# Compass.net
KiCad netlist of a schematic drawn in EAGLE
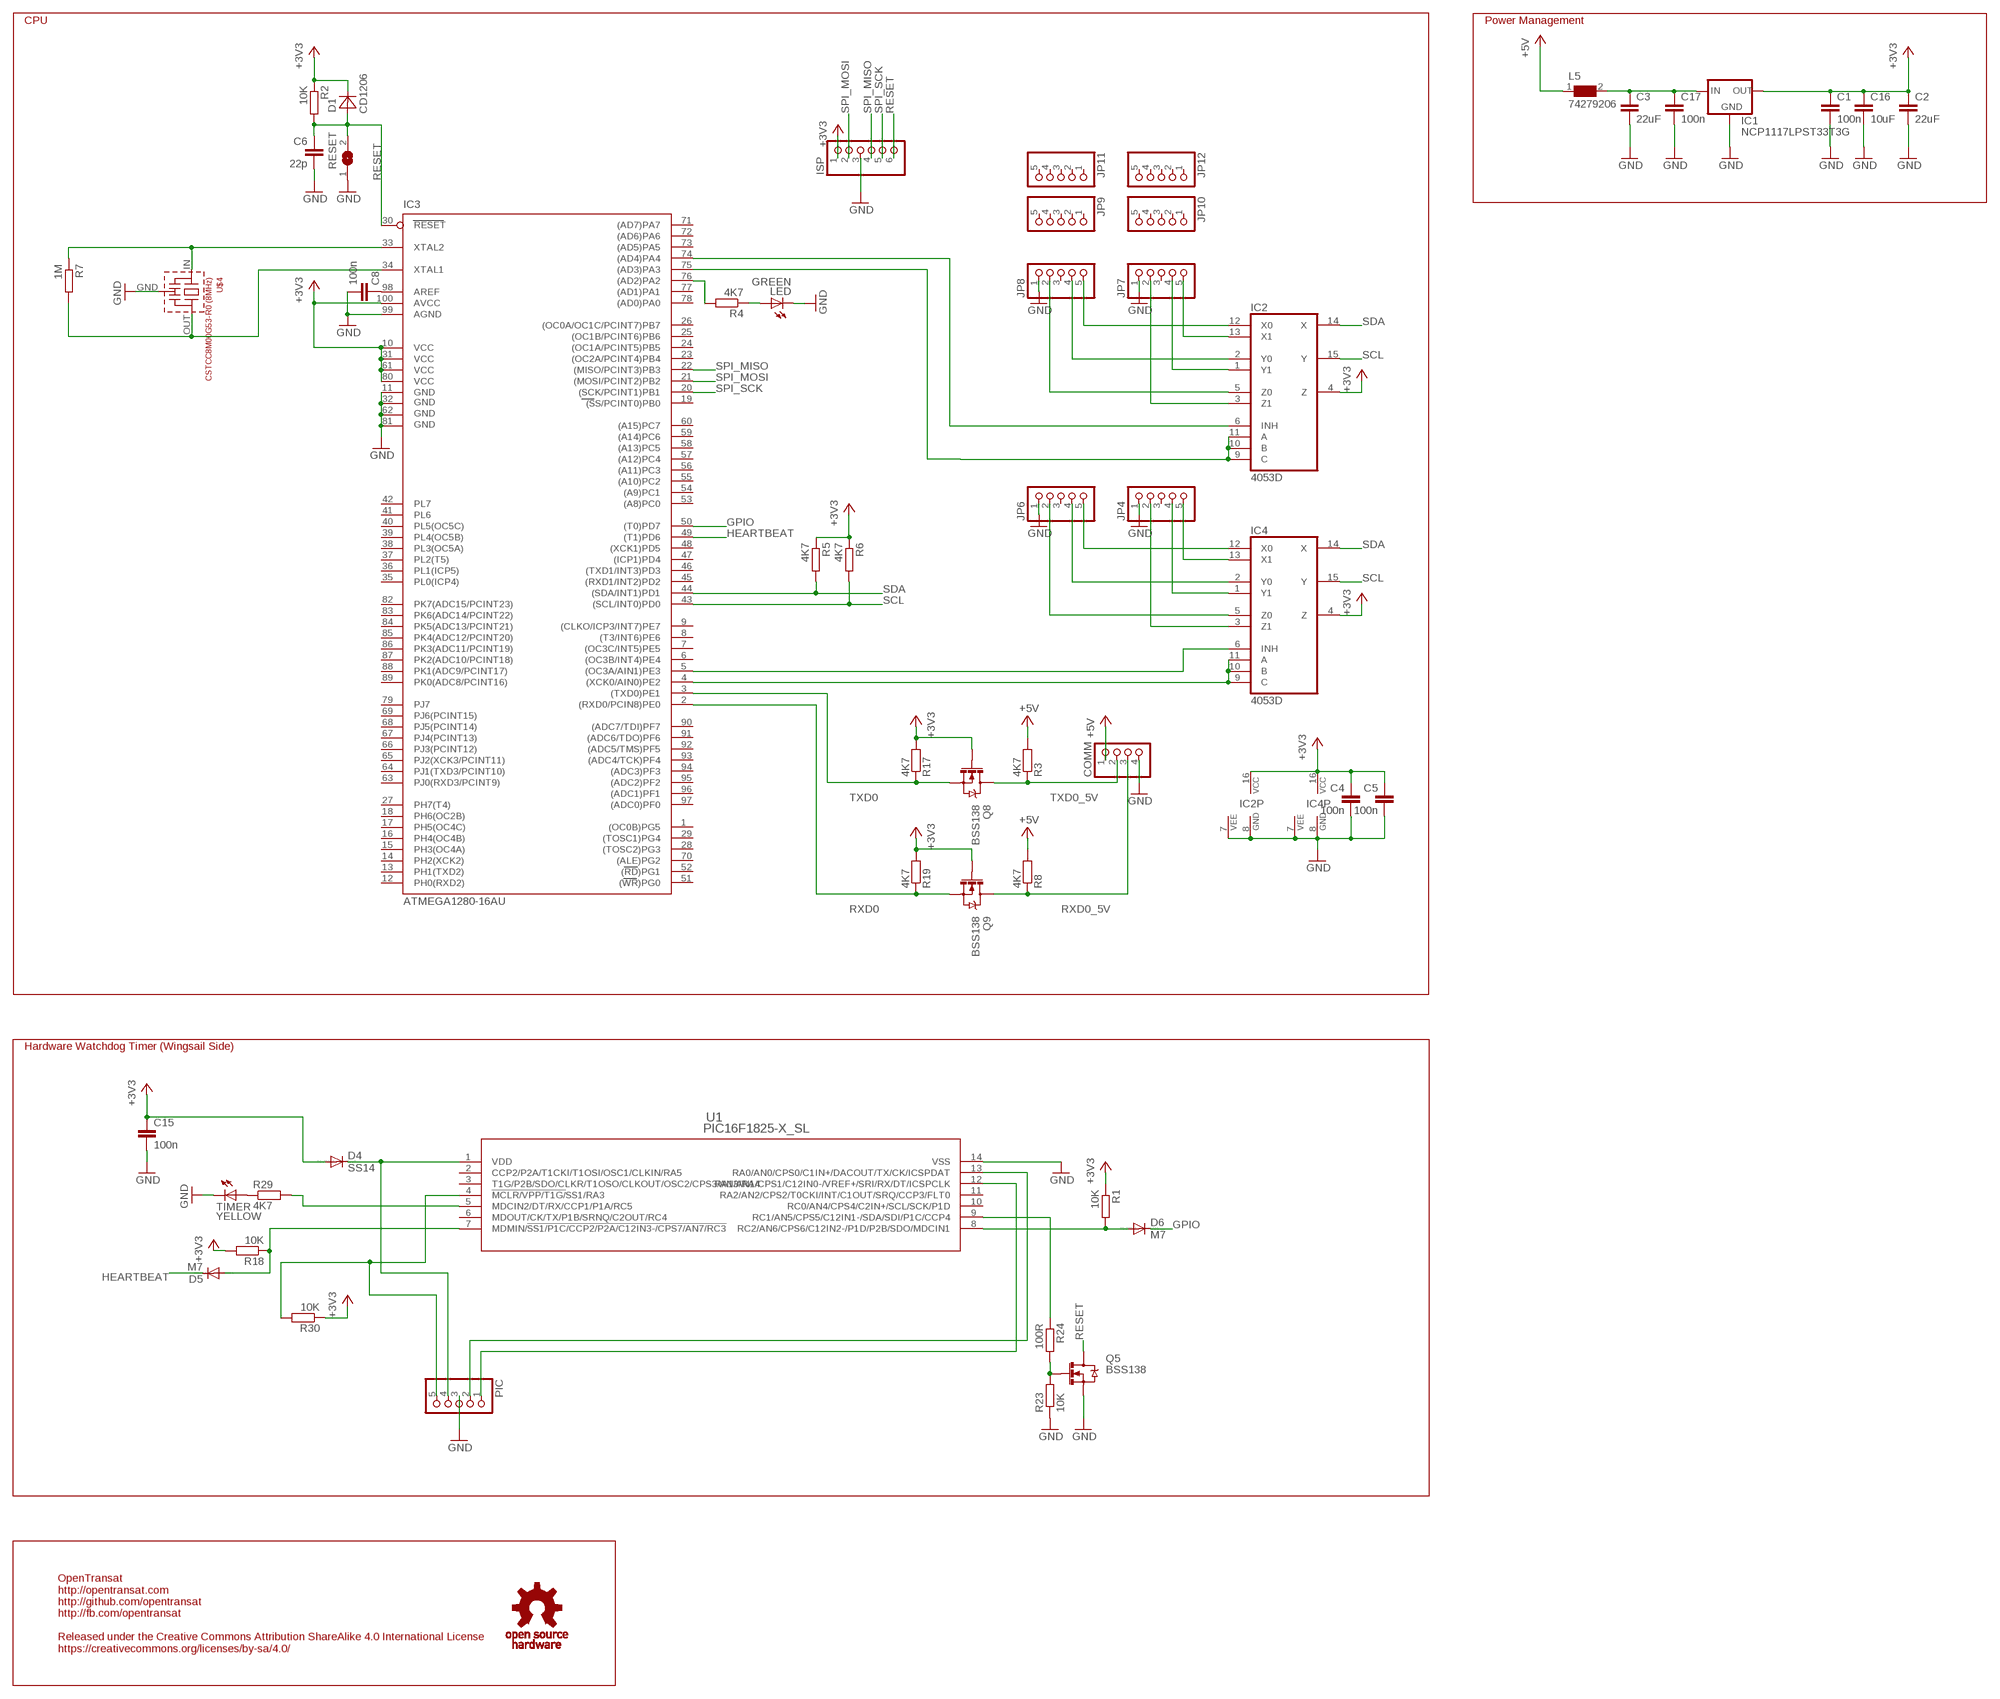
[diagram p0: schematic, sheet 1]

(export (version "E")
  (design (tool "Eeschema 10.0.6"))
  (components
    (comp (ref "C1")
      (value "100n")
      (footprint "eagle-import:C0603")
      (libsource (lib "eagle-import") (part "C-EUC0603"))
    )
    (comp (ref "C2")
      (value "22uF")
      (footprint "eagle-import:C1210")
      (libsource (lib "eagle-import") (part "C-EUC1210"))
    )
    (comp (ref "C3")
      (value "22uF")
      (footprint "eagle-import:C1210")
      (libsource (lib "eagle-import") (part "C-EUC1210"))
    )
    (comp (ref "C4")
      (value "100n")
      (footprint "eagle-import:C0603")
      (libsource (lib "eagle-import") (part "C-EUC0603"))
    )
    (comp (ref "C5")
      (value "100n")
      (footprint "eagle-import:C0603")
      (libsource (lib "eagle-import") (part "C-EUC0603"))
    )
    (comp (ref "C6")
      (value "22p")
      (footprint "eagle-import:C0603")
      (libsource (lib "eagle-import") (part "C-EUC0603"))
    )
    (comp (ref "C8")
      (value "100n")
      (footprint "eagle-import:C0603")
      (libsource (lib "eagle-import") (part "C-EUC0603"))
    )
    (comp (ref "C15")
      (value "100n")
      (footprint "eagle-import:C0603")
      (libsource (lib "eagle-import") (part "C-EUC0603"))
    )
    (comp (ref "C16")
      (value "10uF")
      (footprint "eagle-import:C1206")
      (libsource (lib "eagle-import") (part "C-EUC1206"))
    )
    (comp (ref "C17")
      (value "100n")
      (footprint "eagle-import:C0603")
      (libsource (lib "eagle-import") (part "C-EUC0603"))
    )
    (comp (ref "COMM")
      (value "PINHD-1X4/90")
      (footprint "eagle-import:1X04_90")
      (libsource (lib "eagle-import") (part "PINHD-1X4/90"))
    )
    (comp (ref "D1")
      (value "CD1206")
      (footprint "eagle-import:R1206")
      (libsource (lib "eagle-import") (part "CD1206"))
    )
    (comp (ref "D4")
      (value "SS14")
      (footprint "eagle-import:DO214AC")
      (libsource (lib "eagle-import") (part "DIODE-DO214AC"))
    )
    (comp (ref "D5")
      (value "M7")
      (footprint "eagle-import:DO-214AC")
      (libsource (lib "eagle-import") (part "DIODE-DO-214AC"))
    )
    (comp (ref "D6")
      (value "M7")
      (footprint "eagle-import:DO-214AC")
      (libsource (lib "eagle-import") (part "DIODE-DO-214AC"))
    )
    (comp (ref "IC1")
      (value "NCP1117LPST33T3G")
      (footprint "eagle-import:SOT223")
      (fields (field (name "MF") "Texas Instruments") (field (name "MPN") "LM1117MP-3.3"))
      (libsource (lib "eagle-import") (part "LM1117?-MP3.3"))
    )
    (comp (ref "IC2")
      (value "4053D")
      (footprint "eagle-import:SO16")
      (libsource (lib "eagle-import") (part "4053D"))
    )
    (comp (ref "IC3")
      (value "ATMEGA1280-16AU")
      (footprint "eagle-import:TQFP100")
      (libsource (lib "eagle-import") (part "ATMEGAAU1280-16"))
    )
    (comp (ref "IC4")
      (value "4053D")
      (footprint "eagle-import:SO16")
      (libsource (lib "eagle-import") (part "4053D"))
    )
    (comp (ref "ISP")
      (value "PINHD-1X6/90")
      (footprint "eagle-import:1X06_90")
      (libsource (lib "eagle-import") (part "PINHD-1X6/90"))
    )
    (comp (ref "JP4")
      (value "PINHD-1X5")
      (footprint "eagle-import:1X05")
      (libsource (lib "eagle-import") (part "PINHD-1X5"))
    )
    (comp (ref "JP6")
      (value "PINHD-1X5")
      (footprint "eagle-import:1X05")
      (libsource (lib "eagle-import") (part "PINHD-1X5"))
    )
    (comp (ref "JP7")
      (value "PINHD-1X5")
      (footprint "eagle-import:1X05")
      (libsource (lib "eagle-import") (part "PINHD-1X5"))
    )
    (comp (ref "JP8")
      (value "PINHD-1X5")
      (footprint "eagle-import:1X05")
      (libsource (lib "eagle-import") (part "PINHD-1X5"))
    )
    (comp (ref "JP9")
      (value "PINHD-1X5")
      (footprint "eagle-import:1X05")
      (libsource (lib "eagle-import") (part "PINHD-1X5"))
    )
    (comp (ref "JP10")
      (value "PINHD-1X5")
      (footprint "eagle-import:1X05")
      (libsource (lib "eagle-import") (part "PINHD-1X5"))
    )
    (comp (ref "JP11")
      (value "PINHD-1X5")
      (footprint "eagle-import:1X05")
      (libsource (lib "eagle-import") (part "PINHD-1X5"))
    )
    (comp (ref "JP12")
      (value "PINHD-1X5")
      (footprint "eagle-import:1X05")
      (libsource (lib "eagle-import") (part "PINHD-1X5"))
    )
    (comp (ref "L5")
      (value "74279206")
      (footprint "eagle-import:0805")
      (libsource (lib "eagle-import") (part "WE-CBF_0805"))
    )
    (comp (ref "LED")
      (value "GREEN")
      (footprint "eagle-import:CHIPLED_0805")
      (libsource (lib "eagle-import") (part "LEDCHIPLED_0805"))
    )
    (comp (ref "PIC")
      (value "PINHD-1X5/90")
      (footprint "eagle-import:1X05_90")
      (libsource (lib "eagle-import") (part "PINHD-1X5/90"))
    )
    (comp (ref "Q5")
      (value "BSS138")
      (footprint "eagle-import:SOT23-3")
      (libsource (lib "eagle-import") (part "MOSFET-NCHANNEL_SOT23-3"))
    )
    (comp (ref "Q8")
      (value "BSS138")
      (footprint "eagle-import:SOT23-3")
      (libsource (lib "eagle-import") (part "MOSFET-NCHANNEL_SOT23-3"))
    )
    (comp (ref "Q9")
      (value "BSS138")
      (footprint "eagle-import:SOT23-3")
      (libsource (lib "eagle-import") (part "MOSFET-NCHANNEL_SOT23-3"))
    )
    (comp (ref "R1")
      (value "10K")
      (footprint "eagle-import:R0603")
      (libsource (lib "eagle-import") (part "R-EU_R0603"))
    )
    (comp (ref "R2")
      (value "10K")
      (footprint "eagle-import:R0603")
      (libsource (lib "eagle-import") (part "R-EU_R0603"))
    )
    (comp (ref "R3")
      (value "4K7")
      (footprint "eagle-import:R0603")
      (libsource (lib "eagle-import") (part "R-EU_R0603"))
    )
    (comp (ref "R4")
      (value "4K7")
      (footprint "eagle-import:R0603")
      (libsource (lib "eagle-import") (part "R-EU_R0603"))
    )
    (comp (ref "R5")
      (value "4K7")
      (footprint "eagle-import:R0603")
      (libsource (lib "eagle-import") (part "R-EU_R0603"))
    )
    (comp (ref "R6")
      (value "4K7")
      (footprint "eagle-import:R0603")
      (libsource (lib "eagle-import") (part "R-EU_R0603"))
    )
    (comp (ref "R7")
      (value "1M")
      (footprint "eagle-import:R0603")
      (libsource (lib "eagle-import") (part "R-EU_R0603"))
    )
    (comp (ref "R8")
      (value "4K7")
      (footprint "eagle-import:R0603")
      (libsource (lib "eagle-import") (part "R-EU_R0603"))
    )
    (comp (ref "R17")
      (value "4K7")
      (footprint "eagle-import:R0603")
      (libsource (lib "eagle-import") (part "R-EU_R0603"))
    )
    (comp (ref "R18")
      (value "10K")
      (footprint "eagle-import:R0603")
      (libsource (lib "eagle-import") (part "R-EU_R0603"))
    )
    (comp (ref "R19")
      (value "4K7")
      (footprint "eagle-import:R0603")
      (libsource (lib "eagle-import") (part "R-EU_R0603"))
    )
    (comp (ref "R23")
      (value "10K")
      (footprint "eagle-import:R0603")
      (libsource (lib "eagle-import") (part "R-EU_R0603"))
    )
    (comp (ref "R24")
      (value "100R")
      (footprint "eagle-import:R0603")
      (libsource (lib "eagle-import") (part "R-EU_R0603"))
    )
    (comp (ref "R29")
      (value "4K7")
      (footprint "eagle-import:R0603")
      (libsource (lib "eagle-import") (part "R-EU_R0603"))
    )
    (comp (ref "R30")
      (value "10K")
      (footprint "eagle-import:R0603")
      (libsource (lib "eagle-import") (part "R-EU_R0603"))
    )
    (comp (ref "RESET")
      (value "SJW")
      (footprint "eagle-import:SJW")
      (libsource (lib "eagle-import") (part "SJW"))
    )
    (comp (ref "TIMER")
      (value "YELLOW")
      (footprint "eagle-import:CHIPLED_0805")
      (libsource (lib "eagle-import") (part "LEDCHIPLED_0805"))
    )
    (comp (ref "U$1")
      (value "OSHW_S")
      (footprint "eagle-import:OSHWS")
      (libsource (lib "eagle-import") (part "OSHW_S"))
    )
    (comp (ref "U$4")
      (value "CSTCC8M00G53-R0 (8MHz)")
      (footprint "eagle-import:CSTCC")
      (libsource (lib "eagle-import") (part "CSTCC"))
    )
    (comp (ref "U1")
      (value "PIC16F1825-X_SL")
      (footprint "eagle-import:SOIC14-N_MC")
      (libsource (lib "eagle-import") (part "PIC16F1825-X_SL"))
    )
  )
  (nets
    (net (code "1") (name "+3V3") (class "Default")
      (node (ref "C1") (pin "1") (pinfunction "1_1") (pintype "passive"))
      (node (ref "C15") (pin "1") (pinfunction "1_1") (pintype "passive"))
      (node (ref "C16") (pin "1") (pinfunction "1_1") (pintype "passive"))
      (node (ref "C2") (pin "1") (pinfunction "1_1") (pintype "passive"))
      (node (ref "C4") (pin "1") (pinfunction "1_1") (pintype "passive"))
      (node (ref "C5") (pin "1") (pinfunction "1_1") (pintype "passive"))
      (node (ref "D1") (pin "2") (pinfunction "C_2") (pintype "passive"))
      (node (ref "D4") (pin "A") (pinfunction "A_A") (pintype "passive"))
      (node (ref "IC1") (pin "2") (pinfunction "OUT_2") (pintype "passive"))
      (node (ref "IC1") (pin "4") (pinfunction "OUT_4") (pintype "passive"))
      (node (ref "IC2") (pin "16") (pinfunction "VCC_16") (pintype "power_in"))
      (node (ref "IC2") (pin "4") (pinfunction "Z_4") (pintype "bidirectional"))
      (node (ref "IC3") (pin "10") (pinfunction "VCC_10") (pintype "power_in"))
      (node (ref "IC3") (pin "100") (pinfunction "AVCC_100") (pintype "power_in"))
      (node (ref "IC3") (pin "31") (pinfunction "VCC1_31") (pintype "power_in"))
      (node (ref "IC3") (pin "61") (pinfunction "VCC2_61") (pintype "power_in"))
      (node (ref "IC3") (pin "80") (pinfunction "VCC3_80") (pintype "power_in"))
      (node (ref "IC4") (pin "16") (pinfunction "VCC_16") (pintype "power_in"))
      (node (ref "IC4") (pin "4") (pinfunction "Z_4") (pintype "bidirectional"))
      (node (ref "ISP") (pin "1") (pinfunction "1_1") (pintype "passive"))
      (node (ref "Q8") (pin "1") (pinfunction "G_1") (pintype "passive"))
      (node (ref "Q9") (pin "1") (pinfunction "G_1") (pintype "passive"))
      (node (ref "R1") (pin "1") (pinfunction "1_1") (pintype "passive"))
      (node (ref "R17") (pin "2") (pinfunction "2_2") (pintype "passive"))
      (node (ref "R18") (pin "2") (pinfunction "2_2") (pintype "passive"))
      (node (ref "R19") (pin "2") (pinfunction "2_2") (pintype "passive"))
      (node (ref "R2") (pin "1") (pinfunction "1_1") (pintype "passive"))
      (node (ref "R30") (pin "1") (pinfunction "1_1") (pintype "passive"))
      (node (ref "R5") (pin "1") (pinfunction "1_1") (pintype "passive"))
      (node (ref "R6") (pin "1") (pinfunction "1_1") (pintype "passive"))
    )
    (net (code "2") (name "+5V") (class "Default")
      (node (ref "COMM") (pin "1") (pinfunction "1_1") (pintype "passive"))
      (node (ref "L5") (pin "1") (pinfunction "1_1") (pintype "passive"))
      (node (ref "R3") (pin "2") (pinfunction "2_2") (pintype "passive"))
      (node (ref "R8") (pin "2") (pinfunction "2_2") (pintype "passive"))
    )
    (net (code "3") (name "/GPIO") (class "Default")
      (node (ref "D6") (pin "C") (pinfunction "C_C") (pintype "passive"))
      (node (ref "IC3") (pin "50") (pinfunction "(T0)PD7_50") (pintype "bidirectional"))
    )
    (net (code "4") (name "/HEARTBEAT") (class "Default")
      (node (ref "D5") (pin "C") (pinfunction "C_C") (pintype "passive"))
      (node (ref "IC3") (pin "49") (pinfunction "(T1)PD6_49") (pintype "bidirectional"))
    )
    (net (code "5") (name "/RESET") (class "Default")
      (node (ref "C6") (pin "1") (pinfunction "1_1") (pintype "passive"))
      (node (ref "D1") (pin "1") (pinfunction "A_1") (pintype "passive"))
      (node (ref "IC3") (pin "30") (pinfunction "RESET_30") (pintype "input"))
      (node (ref "ISP") (pin "6") (pinfunction "6_6") (pintype "passive"))
      (node (ref "Q5") (pin "3") (pinfunction "D_3") (pintype "passive"))
      (node (ref "R2") (pin "2") (pinfunction "2_2") (pintype "passive"))
      (node (ref "RESET") (pin "2") (pinfunction "2_2") (pintype "passive"))
    )
    (net (code "6") (name "/RXD0") (class "Default")
      (node (ref "IC3") (pin "2") (pinfunction "(RXD0/PCIN8)PE0_2") (pintype "bidirectional"))
      (node (ref "Q9") (pin "2") (pinfunction "S_2") (pintype "passive"))
      (node (ref "R19") (pin "1") (pinfunction "1_1") (pintype "passive"))
    )
    (net (code "7") (name "/RXD0_5V") (class "Default")
      (node (ref "COMM") (pin "3") (pinfunction "3_3") (pintype "passive"))
      (node (ref "Q9") (pin "3") (pinfunction "D_3") (pintype "passive"))
      (node (ref "R8") (pin "1") (pinfunction "1_1") (pintype "passive"))
    )
    (net (code "8") (name "/SCL") (class "Default")
      (node (ref "IC2") (pin "15") (pinfunction "Y_15") (pintype "bidirectional"))
      (node (ref "IC3") (pin "43") (pinfunction "(SCL/INT0)PD0_43") (pintype "bidirectional"))
      (node (ref "IC4") (pin "15") (pinfunction "Y_15") (pintype "bidirectional"))
      (node (ref "R6") (pin "2") (pinfunction "2_2") (pintype "passive"))
    )
    (net (code "9") (name "/SDA") (class "Default")
      (node (ref "IC2") (pin "14") (pinfunction "X_14") (pintype "bidirectional"))
      (node (ref "IC3") (pin "44") (pinfunction "(SDA/INT1)PD1_44") (pintype "bidirectional"))
      (node (ref "IC4") (pin "14") (pinfunction "X_14") (pintype "bidirectional"))
      (node (ref "R5") (pin "2") (pinfunction "2_2") (pintype "passive"))
    )
    (net (code "10") (name "/SPI_MISO") (class "Default")
      (node (ref "IC3") (pin "22") (pinfunction "(MISO/PCINT3)PB3_22") (pintype "bidirectional"))
      (node (ref "ISP") (pin "4") (pinfunction "4_4") (pintype "passive"))
    )
    (net (code "11") (name "/SPI_MOSI") (class "Default")
      (node (ref "IC3") (pin "21") (pinfunction "(MOSI/PCINT2)PB2_21") (pintype "bidirectional"))
      (node (ref "ISP") (pin "2") (pinfunction "2_2") (pintype "passive"))
    )
    (net (code "12") (name "/SPI_SCK") (class "Default")
      (node (ref "IC3") (pin "20") (pinfunction "(SCK/PCINT1)PB1_20") (pintype "bidirectional"))
      (node (ref "ISP") (pin "5") (pinfunction "5_5") (pintype "passive"))
    )
    (net (code "13") (name "/TXD0") (class "Default")
      (node (ref "IC3") (pin "3") (pinfunction "(TXD0)PE1_3") (pintype "bidirectional"))
      (node (ref "Q8") (pin "2") (pinfunction "S_2") (pintype "passive"))
      (node (ref "R17") (pin "1") (pinfunction "1_1") (pintype "passive"))
    )
    (net (code "14") (name "/TXD0_5V") (class "Default")
      (node (ref "COMM") (pin "2") (pinfunction "2_2") (pintype "passive"))
      (node (ref "Q8") (pin "3") (pinfunction "D_3") (pintype "passive"))
      (node (ref "R3") (pin "1") (pinfunction "1_1") (pintype "passive"))
    )
    (net (code "15") (name "GND") (class "Default")
      (node (ref "C1") (pin "2") (pinfunction "2_2") (pintype "passive"))
      (node (ref "C15") (pin "2") (pinfunction "2_2") (pintype "passive"))
      (node (ref "C16") (pin "2") (pinfunction "2_2") (pintype "passive"))
      (node (ref "C17") (pin "2") (pinfunction "2_2") (pintype "passive"))
      (node (ref "C2") (pin "2") (pinfunction "2_2") (pintype "passive"))
      (node (ref "C3") (pin "2") (pinfunction "2_2") (pintype "passive"))
      (node (ref "C4") (pin "2") (pinfunction "2_2") (pintype "passive"))
      (node (ref "C5") (pin "2") (pinfunction "2_2") (pintype "passive"))
      (node (ref "C6") (pin "2") (pinfunction "2_2") (pintype "passive"))
      (node (ref "C8") (pin "2") (pinfunction "2_2") (pintype "passive"))
      (node (ref "COMM") (pin "4") (pinfunction "4_4") (pintype "passive"))
      (node (ref "IC1") (pin "1") (pinfunction "GND_1") (pintype "input"))
      (node (ref "IC2") (pin "7") (pinfunction "VEE_7") (pintype "power_in"))
      (node (ref "IC2") (pin "8") (pinfunction "GND_8") (pintype "power_in"))
      (node (ref "IC3") (pin "11") (pinfunction "GND_11") (pintype "power_in"))
      (node (ref "IC3") (pin "32") (pinfunction "GND1_32") (pintype "power_in"))
      (node (ref "IC3") (pin "62") (pinfunction "GND2_62") (pintype "power_in"))
      (node (ref "IC3") (pin "81") (pinfunction "GND3_81") (pintype "power_in"))
      (node (ref "IC3") (pin "99") (pinfunction "AGND_99") (pintype "power_in"))
      (node (ref "IC4") (pin "7") (pinfunction "VEE_7") (pintype "power_in"))
      (node (ref "IC4") (pin "8") (pinfunction "GND_8") (pintype "power_in"))
      (node (ref "ISP") (pin "3") (pinfunction "3_3") (pintype "passive"))
      (node (ref "JP4") (pin "1") (pinfunction "1_1") (pintype "passive"))
      (node (ref "JP6") (pin "1") (pinfunction "1_1") (pintype "passive"))
      (node (ref "JP7") (pin "1") (pinfunction "1_1") (pintype "passive"))
      (node (ref "JP8") (pin "1") (pinfunction "1_1") (pintype "passive"))
      (node (ref "LED") (pin "C") (pinfunction "C_C") (pintype "passive"))
      (node (ref "PIC") (pin "3") (pinfunction "3_3") (pintype "passive"))
      (node (ref "Q5") (pin "2") (pinfunction "S_2") (pintype "passive"))
      (node (ref "R23") (pin "1") (pinfunction "1_1") (pintype "passive"))
      (node (ref "RESET") (pin "1") (pinfunction "1_1") (pintype "passive"))
      (node (ref "TIMER") (pin "C") (pinfunction "C_C") (pintype "passive"))
      (node (ref "U$4") (pin "GND") (pinfunction "GND_GND") (pintype "power_in"))
      (node (ref "U1") (pin "14") (pinfunction "VSS_14") (pintype "power_in"))
    )
    (net (code "16") (name "Net-(IC1-IN)") (class "Default")
      (node (ref "C17") (pin "1") (pinfunction "1_1") (pintype "passive"))
      (node (ref "C3") (pin "1") (pinfunction "1_1") (pintype "passive"))
      (node (ref "IC1") (pin "3") (pinfunction "IN_3") (pintype "input"))
      (node (ref "L5") (pin "2") (pinfunction "2_2") (pintype "passive"))
    )
    (net (code "17") (name "Net-(IC2A-A)") (class "Default")
      (node (ref "IC2") (pin "10") (pinfunction "B_10") (pintype "input"))
      (node (ref "IC2") (pin "11") (pinfunction "A_11") (pintype "input"))
      (node (ref "IC2") (pin "9") (pinfunction "C_9") (pintype "input"))
      (node (ref "IC3") (pin "75") (pinfunction "(AD3)PA3_75") (pintype "bidirectional"))
    )
    (net (code "18") (name "Net-(IC2A-INH)") (class "Default")
      (node (ref "IC2") (pin "6") (pinfunction "INH_6") (pintype "input"))
      (node (ref "IC3") (pin "74") (pinfunction "(AD4)PA4_74") (pintype "bidirectional"))
    )
    (net (code "19") (name "Net-(IC2A-X0)") (class "Default")
      (node (ref "IC2") (pin "12") (pinfunction "X0_12") (pintype "bidirectional"))
      (node (ref "JP8") (pin "5") (pinfunction "5_5") (pintype "passive"))
    )
    (net (code "20") (name "Net-(IC2A-X1)") (class "Default")
      (node (ref "IC2") (pin "13") (pinfunction "X1_13") (pintype "bidirectional"))
      (node (ref "JP7") (pin "5") (pinfunction "5_5") (pintype "passive"))
    )
    (net (code "21") (name "Net-(IC2A-Y0)") (class "Default")
      (node (ref "IC2") (pin "2") (pinfunction "Y0_2") (pintype "bidirectional"))
      (node (ref "JP8") (pin "4") (pinfunction "4_4") (pintype "passive"))
    )
    (net (code "22") (name "Net-(IC2A-Y1)") (class "Default")
      (node (ref "IC2") (pin "1") (pinfunction "Y1_1") (pintype "bidirectional"))
      (node (ref "JP7") (pin "4") (pinfunction "4_4") (pintype "passive"))
    )
    (net (code "23") (name "Net-(IC2A-Z0)") (class "Default")
      (node (ref "IC2") (pin "5") (pinfunction "Z0_5") (pintype "bidirectional"))
      (node (ref "JP8") (pin "2") (pinfunction "2_2") (pintype "passive"))
    )
    (net (code "24") (name "Net-(IC2A-Z1)") (class "Default")
      (node (ref "IC2") (pin "3") (pinfunction "Z1_3") (pintype "bidirectional"))
      (node (ref "JP7") (pin "2") (pinfunction "2_2") (pintype "passive"))
    )
    (net (code "25") (name "Net-(IC3-(AD2)PA2)") (class "Default")
      (node (ref "IC3") (pin "76") (pinfunction "(AD2)PA2_76") (pintype "bidirectional"))
      (node (ref "R4") (pin "2") (pinfunction "2_2") (pintype "passive"))
    )
    (net (code "26") (name "Net-(IC3-(OC3A{slash}AIN1)PE3)") (class "Default")
      (node (ref "IC3") (pin "5") (pinfunction "(OC3A/AIN1)PE3_5") (pintype "bidirectional"))
      (node (ref "IC4") (pin "6") (pinfunction "INH_6") (pintype "input"))
    )
    (net (code "27") (name "Net-(IC3-(XCK0{slash}AIN0)PE2)") (class "Default")
      (node (ref "IC3") (pin "4") (pinfunction "(XCK0/AIN0)PE2_4") (pintype "bidirectional"))
      (node (ref "IC4") (pin "10") (pinfunction "B_10") (pintype "input"))
      (node (ref "IC4") (pin "11") (pinfunction "A_11") (pintype "input"))
      (node (ref "IC4") (pin "9") (pinfunction "C_9") (pintype "input"))
    )
    (net (code "28") (name "Net-(IC3-AREF)") (class "Default")
      (node (ref "C8") (pin "1") (pinfunction "1_1") (pintype "passive"))
      (node (ref "IC3") (pin "98") (pinfunction "AREF_98") (pintype "bidirectional"))
    )
    (net (code "29") (name "Net-(IC3-XTAL1)") (class "Default")
      (node (ref "IC3") (pin "34") (pinfunction "XTAL1_34") (pintype "input"))
      (node (ref "R7") (pin "2") (pinfunction "2_2") (pintype "passive"))
      (node (ref "U$4") (pin "OUT") (pinfunction "OUT_OUT") (pintype "output"))
    )
    (net (code "30") (name "Net-(IC3-XTAL2)") (class "Default")
      (node (ref "IC3") (pin "33") (pinfunction "XTAL2_33") (pintype "output"))
      (node (ref "R7") (pin "1") (pinfunction "1_1") (pintype "passive"))
      (node (ref "U$4") (pin "IN") (pinfunction "IN_IN") (pintype "input"))
    )
    (net (code "31") (name "Net-(IC4A-X0)") (class "Default")
      (node (ref "IC4") (pin "12") (pinfunction "X0_12") (pintype "bidirectional"))
      (node (ref "JP6") (pin "5") (pinfunction "5_5") (pintype "passive"))
    )
    (net (code "32") (name "Net-(IC4A-X1)") (class "Default")
      (node (ref "IC4") (pin "13") (pinfunction "X1_13") (pintype "bidirectional"))
      (node (ref "JP4") (pin "5") (pinfunction "5_5") (pintype "passive"))
    )
    (net (code "33") (name "Net-(IC4A-Y0)") (class "Default")
      (node (ref "IC4") (pin "2") (pinfunction "Y0_2") (pintype "bidirectional"))
      (node (ref "JP6") (pin "4") (pinfunction "4_4") (pintype "passive"))
    )
    (net (code "34") (name "Net-(IC4A-Y1)") (class "Default")
      (node (ref "IC4") (pin "1") (pinfunction "Y1_1") (pintype "bidirectional"))
      (node (ref "JP4") (pin "4") (pinfunction "4_4") (pintype "passive"))
    )
    (net (code "35") (name "Net-(IC4A-Z0)") (class "Default")
      (node (ref "IC4") (pin "5") (pinfunction "Z0_5") (pintype "bidirectional"))
      (node (ref "JP6") (pin "2") (pinfunction "2_2") (pintype "passive"))
    )
    (net (code "36") (name "Net-(IC4A-Z1)") (class "Default")
      (node (ref "IC4") (pin "3") (pinfunction "Z1_3") (pintype "bidirectional"))
      (node (ref "JP4") (pin "2") (pinfunction "2_2") (pintype "passive"))
    )
    (net (code "37") (name "Net-(LED-PadA)") (class "Default")
      (node (ref "LED") (pin "A") (pinfunction "A_A") (pintype "passive"))
      (node (ref "R4") (pin "1") (pinfunction "1_1") (pintype "passive"))
    )
    (net (code "38") (name "Net-(Q5-G)") (class "Default")
      (node (ref "Q5") (pin "1") (pinfunction "G_1") (pintype "passive"))
      (node (ref "R23") (pin "2") (pinfunction "2_2") (pintype "passive"))
      (node (ref "R24") (pin "2") (pinfunction "2_2") (pintype "passive"))
    )
    (net (code "39") (name "Net-(R29-Pad1)") (class "Default")
      (node (ref "R29") (pin "1") (pinfunction "1_1") (pintype "passive"))
      (node (ref "TIMER") (pin "A") (pinfunction "A_A") (pintype "passive"))
    )
    (net (code "40") (name "Net-(U1-MDCIN2{slash}DT{slash}RX{slash}CCP1{slash}P1A{slash}RC5)") (class "Default")
      (node (ref "R29") (pin "2") (pinfunction "2_2") (pintype "passive"))
      (node (ref "U1") (pin "5") (pinfunction "MDCIN2/DT/RX/CCP1/P1A/RC5_5") (pintype "bidirectional"))
    )
    (net (code "41") (name "Net-(U1-MDMIN{slash}~{SS1{slash}P1C{slash}CCP2{slash}P2A{slash}C12IN3-{slash}CPS7{slash}AN7{slash}RC3})") (class "Default")
      (node (ref "D5") (pin "A") (pinfunction "A_A") (pintype "passive"))
      (node (ref "R18") (pin "1") (pinfunction "1_1") (pintype "passive"))
      (node (ref "U1") (pin "7") (pinfunction "MDMIN/~{SS1/P1C/CCP2/P2A/C12IN3-/CPS7/AN7/RC3}_7") (pintype "bidirectional"))
    )
    (net (code "42") (name "Net-(U1-RA0{slash}AN0{slash}CPS0{slash}C1IN+{slash}DACOUT{slash}TX{slash}CK{slash}ICSPDAT)") (class "Default")
      (node (ref "PIC") (pin "2") (pinfunction "2_2") (pintype "passive"))
      (node (ref "U1") (pin "13") (pinfunction "RA0/AN0/CPS0/C1IN+/DACOUT/TX/CK/ICSPDAT_13") (pintype "bidirectional"))
    )
    (net (code "43") (name "Net-(U1-RA1{slash}AN1{slash}CPS1{slash}C12IN0-{slash}VREF+{slash}SRI{slash}RX{slash}DT{slash}ICSPCLK)") (class "Default")
      (node (ref "PIC") (pin "1") (pinfunction "1_1") (pintype "passive"))
      (node (ref "U1") (pin "12") (pinfunction "RA1/AN1/CPS1/C12IN0-/VREF+/SRI/RX/DT/ICSPCLK_12") (pintype "bidirectional"))
    )
    (net (code "44") (name "Net-(U1-RC1{slash}AN5{slash}CPS5{slash}C12IN1-{slash}SDA{slash}SDI{slash}P1C{slash}CCP4)") (class "Default")
      (node (ref "R24") (pin "1") (pinfunction "1_1") (pintype "passive"))
      (node (ref "U1") (pin "9") (pinfunction "RC1/AN5/CPS5/C12IN1-/SDA/SDI/P1C/CCP4_9") (pintype "bidirectional"))
    )
    (net (code "45") (name "Net-(U1-RC2{slash}AN6{slash}CPS6{slash}C12IN2-{slash}P1D{slash}P2B{slash}SDO{slash}MDCIN1)") (class "Default")
      (node (ref "D6") (pin "A") (pinfunction "A_A") (pintype "passive"))
      (node (ref "R1") (pin "2") (pinfunction "2_2") (pintype "passive"))
      (node (ref "U1") (pin "8") (pinfunction "RC2/AN6/CPS6/C12IN2-/P1D/P2B/SDO/MDCIN1_8") (pintype "bidirectional"))
    )
    (net (code "46") (name "Net-(U1-VDD)") (class "Default")
      (node (ref "D4") (pin "C") (pinfunction "C_C") (pintype "passive"))
      (node (ref "PIC") (pin "4") (pinfunction "4_4") (pintype "passive"))
      (node (ref "U1") (pin "1") (pinfunction "VDD_1") (pintype "power_in"))
    )
    (net (code "47") (name "Net-(U1-~{MCLR{slash}VPP{slash}T1G{slash}}SS1{slash}RA3)") (class "Default")
      (node (ref "PIC") (pin "5") (pinfunction "5_5") (pintype "passive"))
      (node (ref "R30") (pin "2") (pinfunction "2_2") (pintype "passive"))
      (node (ref "U1") (pin "4") (pinfunction "~{MCLR/VPP/T1G/}SS1/RA3_4") (pintype "bidirectional"))
    )
    (net (code "48") (name "unconnected-(IC3-(A8)PC0-Pad53)") (class "Default")
      (node (ref "IC3") (pin "53") (pinfunction "(A8)PC0_53") (pintype "bidirectional"))
    )
    (net (code "49") (name "unconnected-(IC3-(A9)PC1-Pad54)") (class "Default")
      (node (ref "IC3") (pin "54") (pinfunction "(A9)PC1_54") (pintype "bidirectional"))
    )
    (net (code "50") (name "unconnected-(IC3-(A10)PC2-Pad55)") (class "Default")
      (node (ref "IC3") (pin "55") (pinfunction "(A10)PC2_55") (pintype "bidirectional"))
    )
    (net (code "51") (name "unconnected-(IC3-(A11)PC3-Pad56)") (class "Default")
      (node (ref "IC3") (pin "56") (pinfunction "(A11)PC3_56") (pintype "bidirectional"))
    )
    (net (code "52") (name "unconnected-(IC3-(A12)PC4-Pad57)") (class "Default")
      (node (ref "IC3") (pin "57") (pinfunction "(A12)PC4_57") (pintype "bidirectional"))
    )
    (net (code "53") (name "unconnected-(IC3-(A13)PC5-Pad58)") (class "Default")
      (node (ref "IC3") (pin "58") (pinfunction "(A13)PC5_58") (pintype "bidirectional"))
    )
    (net (code "54") (name "unconnected-(IC3-(A14)PC6-Pad59)") (class "Default")
      (node (ref "IC3") (pin "59") (pinfunction "(A14)PC6_59") (pintype "bidirectional"))
    )
    (net (code "55") (name "unconnected-(IC3-(A15)PC7-Pad60)") (class "Default")
      (node (ref "IC3") (pin "60") (pinfunction "(A15)PC7_60") (pintype "bidirectional"))
    )
    (net (code "56") (name "unconnected-(IC3-(AD0)PA0-Pad78)") (class "Default")
      (node (ref "IC3") (pin "78") (pinfunction "(AD0)PA0_78") (pintype "bidirectional"))
    )
    (net (code "57") (name "unconnected-(IC3-(AD1)PA1-Pad77)") (class "Default")
      (node (ref "IC3") (pin "77") (pinfunction "(AD1)PA1_77") (pintype "bidirectional"))
    )
    (net (code "58") (name "unconnected-(IC3-(AD5)PA5-Pad73)") (class "Default")
      (node (ref "IC3") (pin "73") (pinfunction "(AD5)PA5_73") (pintype "bidirectional"))
    )
    (net (code "59") (name "unconnected-(IC3-(AD6)PA6-Pad72)") (class "Default")
      (node (ref "IC3") (pin "72") (pinfunction "(AD6)PA6_72") (pintype "bidirectional"))
    )
    (net (code "60") (name "unconnected-(IC3-(AD7)PA7-Pad71)") (class "Default")
      (node (ref "IC3") (pin "71") (pinfunction "(AD7)PA7_71") (pintype "bidirectional"))
    )
    (net (code "61") (name "unconnected-(IC3-(ADC0)PF0-Pad97)") (class "Default")
      (node (ref "IC3") (pin "97") (pinfunction "(ADC0)PF0_97") (pintype "bidirectional"))
    )
    (net (code "62") (name "unconnected-(IC3-(ADC1)PF1-Pad96)") (class "Default")
      (node (ref "IC3") (pin "96") (pinfunction "(ADC1)PF1_96") (pintype "bidirectional"))
    )
    (net (code "63") (name "unconnected-(IC3-(ADC2)PF2-Pad95)") (class "Default")
      (node (ref "IC3") (pin "95") (pinfunction "(ADC2)PF2_95") (pintype "bidirectional"))
    )
    (net (code "64") (name "unconnected-(IC3-(ADC3)PF3-Pad94)") (class "Default")
      (node (ref "IC3") (pin "94") (pinfunction "(ADC3)PF3_94") (pintype "bidirectional"))
    )
    (net (code "65") (name "unconnected-(IC3-(ADC4{slash}TCK)PF4-Pad93)") (class "Default")
      (node (ref "IC3") (pin "93") (pinfunction "(ADC4/TCK)PF4_93") (pintype "bidirectional"))
    )
    (net (code "66") (name "unconnected-(IC3-(ADC5{slash}TMS)PF5-Pad92)") (class "Default")
      (node (ref "IC3") (pin "92") (pinfunction "(ADC5/TMS)PF5_92") (pintype "bidirectional"))
    )
    (net (code "67") (name "unconnected-(IC3-(ADC6{slash}TDO)PF6-Pad91)") (class "Default")
      (node (ref "IC3") (pin "91") (pinfunction "(ADC6/TDO)PF6_91") (pintype "bidirectional"))
    )
    (net (code "68") (name "unconnected-(IC3-(ADC7{slash}TDI)PF7-Pad90)") (class "Default")
      (node (ref "IC3") (pin "90") (pinfunction "(ADC7/TDI)PF7_90") (pintype "bidirectional"))
    )
    (net (code "69") (name "unconnected-(IC3-(ALE)PG2-Pad70)") (class "Default")
      (node (ref "IC3") (pin "70") (pinfunction "(ALE)PG2_70") (pintype "bidirectional"))
    )
    (net (code "70") (name "unconnected-(IC3-(CLKO{slash}ICP3{slash}INT7)PE7-Pad9)") (class "Default")
      (node (ref "IC3") (pin "9") (pinfunction "(CLKO/ICP3/INT7)PE7_9") (pintype "bidirectional"))
    )
    (net (code "71") (name "unconnected-(IC3-(ICP1)PD4-Pad47)") (class "Default")
      (node (ref "IC3") (pin "47") (pinfunction "(ICP1)PD4_47") (pintype "bidirectional"))
    )
    (net (code "72") (name "unconnected-(IC3-(OC0A{slash}OC1C{slash}PCINT7)PB7-Pad26)") (class "Default")
      (node (ref "IC3") (pin "26") (pinfunction "(OC0A/OC1C/PCINT7)PB7_26") (pintype "bidirectional"))
    )
    (net (code "73") (name "unconnected-(IC3-(OC0B)PG5-Pad1)") (class "Default")
      (node (ref "IC3") (pin "1") (pinfunction "(OC0B)PG5_1") (pintype "bidirectional"))
    )
    (net (code "74") (name "unconnected-(IC3-(OC1A{slash}PCINT5)PB5-Pad24)") (class "Default")
      (node (ref "IC3") (pin "24") (pinfunction "(OC1A/PCINT5)PB5_24") (pintype "bidirectional"))
    )
    (net (code "75") (name "unconnected-(IC3-(OC1B{slash}PCINT6)PB6-Pad25)") (class "Default")
      (node (ref "IC3") (pin "25") (pinfunction "(OC1B/PCINT6)PB6_25") (pintype "bidirectional"))
    )
    (net (code "76") (name "unconnected-(IC3-(OC2A{slash}PCINT4)PB4-Pad23)") (class "Default")
      (node (ref "IC3") (pin "23") (pinfunction "(OC2A/PCINT4)PB4_23") (pintype "bidirectional"))
    )
    (net (code "77") (name "unconnected-(IC3-(OC3B{slash}INT4)PE4-Pad6)") (class "Default")
      (node (ref "IC3") (pin "6") (pinfunction "(OC3B/INT4)PE4_6") (pintype "bidirectional"))
    )
    (net (code "78") (name "unconnected-(IC3-(OC3C{slash}INT5)PE5-Pad7)") (class "Default")
      (node (ref "IC3") (pin "7") (pinfunction "(OC3C/INT5)PE5_7") (pintype "bidirectional"))
    )
    (net (code "79") (name "unconnected-(IC3-(RD)PG1-Pad52)") (class "Default")
      (node (ref "IC3") (pin "52") (pinfunction "(RD)PG1_52") (pintype "bidirectional"))
    )
    (net (code "80") (name "unconnected-(IC3-(RXD1{slash}INT2)PD2-Pad45)") (class "Default")
      (node (ref "IC3") (pin "45") (pinfunction "(RXD1/INT2)PD2_45") (pintype "bidirectional"))
    )
    (net (code "81") (name "unconnected-(IC3-(SS{slash}PCINT0)PB0-Pad19)") (class "Default")
      (node (ref "IC3") (pin "19") (pinfunction "(SS/PCINT0)PB0_19") (pintype "bidirectional"))
    )
    (net (code "82") (name "unconnected-(IC3-(T3{slash}INT6)PE6-Pad8)") (class "Default")
      (node (ref "IC3") (pin "8") (pinfunction "(T3/INT6)PE6_8") (pintype "bidirectional"))
    )
    (net (code "83") (name "unconnected-(IC3-(TOSC1)PG4-Pad29)") (class "Default")
      (node (ref "IC3") (pin "29") (pinfunction "(TOSC1)PG4_29") (pintype "bidirectional"))
    )
    (net (code "84") (name "unconnected-(IC3-(TOSC2)PG3-Pad28)") (class "Default")
      (node (ref "IC3") (pin "28") (pinfunction "(TOSC2)PG3_28") (pintype "bidirectional"))
    )
    (net (code "85") (name "unconnected-(IC3-(TXD1{slash}INT3)PD3-Pad46)") (class "Default")
      (node (ref "IC3") (pin "46") (pinfunction "(TXD1/INT3)PD3_46") (pintype "bidirectional"))
    )
    (net (code "86") (name "unconnected-(IC3-(WR)PG0-Pad51)") (class "Default")
      (node (ref "IC3") (pin "51") (pinfunction "(WR)PG0_51") (pintype "bidirectional"))
    )
    (net (code "87") (name "unconnected-(IC3-(XCK1)PD5-Pad48)") (class "Default")
      (node (ref "IC3") (pin "48") (pinfunction "(XCK1)PD5_48") (pintype "bidirectional"))
    )
    (net (code "88") (name "unconnected-(IC3-PH0(RXD2)-Pad12)") (class "Default")
      (node (ref "IC3") (pin "12") (pinfunction "PH0(RXD2)_12") (pintype "bidirectional"))
    )
    (net (code "89") (name "unconnected-(IC3-PH1(TXD2)-Pad13)") (class "Default")
      (node (ref "IC3") (pin "13") (pinfunction "PH1(TXD2)_13") (pintype "bidirectional"))
    )
    (net (code "90") (name "unconnected-(IC3-PH2(XCK2)-Pad14)") (class "Default")
      (node (ref "IC3") (pin "14") (pinfunction "PH2(XCK2)_14") (pintype "bidirectional"))
    )
    (net (code "91") (name "unconnected-(IC3-PH3(OC4A)-Pad15)") (class "Default")
      (node (ref "IC3") (pin "15") (pinfunction "PH3(OC4A)_15") (pintype "bidirectional"))
    )
    (net (code "92") (name "unconnected-(IC3-PH4(OC4B)-Pad16)") (class "Default")
      (node (ref "IC3") (pin "16") (pinfunction "PH4(OC4B)_16") (pintype "bidirectional"))
    )
    (net (code "93") (name "unconnected-(IC3-PH5(OC4C)-Pad17)") (class "Default")
      (node (ref "IC3") (pin "17") (pinfunction "PH5(OC4C)_17") (pintype "bidirectional"))
    )
    (net (code "94") (name "unconnected-(IC3-PH6(OC2B)-Pad18)") (class "Default")
      (node (ref "IC3") (pin "18") (pinfunction "PH6(OC2B)_18") (pintype "bidirectional"))
    )
    (net (code "95") (name "unconnected-(IC3-PH7(T4)-Pad27)") (class "Default")
      (node (ref "IC3") (pin "27") (pinfunction "PH7(T4)_27") (pintype "bidirectional"))
    )
    (net (code "96") (name "unconnected-(IC3-PJ0(RXD3{slash}PCINT9)-Pad63)") (class "Default")
      (node (ref "IC3") (pin "63") (pinfunction "PJ0(RXD3/PCINT9)_63") (pintype "bidirectional"))
    )
    (net (code "97") (name "unconnected-(IC3-PJ1(TXD3{slash}PCINT10)-Pad64)") (class "Default")
      (node (ref "IC3") (pin "64") (pinfunction "PJ1(TXD3/PCINT10)_64") (pintype "bidirectional"))
    )
    (net (code "98") (name "unconnected-(IC3-PJ2(XCK3{slash}PCINT11)-Pad65)") (class "Default")
      (node (ref "IC3") (pin "65") (pinfunction "PJ2(XCK3/PCINT11)_65") (pintype "bidirectional"))
    )
    (net (code "99") (name "unconnected-(IC3-PJ3(PCINT12)-Pad66)") (class "Default")
      (node (ref "IC3") (pin "66") (pinfunction "PJ3(PCINT12)_66") (pintype "bidirectional"))
    )
    (net (code "100") (name "unconnected-(IC3-PJ4(PCINT13)-Pad67)") (class "Default")
      (node (ref "IC3") (pin "67") (pinfunction "PJ4(PCINT13)_67") (pintype "bidirectional"))
    )
    (net (code "101") (name "unconnected-(IC3-PJ5(PCINT14)-Pad68)") (class "Default")
      (node (ref "IC3") (pin "68") (pinfunction "PJ5(PCINT14)_68") (pintype "bidirectional"))
    )
    (net (code "102") (name "unconnected-(IC3-PJ6(PCINT15)-Pad69)") (class "Default")
      (node (ref "IC3") (pin "69") (pinfunction "PJ6(PCINT15)_69") (pintype "bidirectional"))
    )
    (net (code "103") (name "unconnected-(IC3-PJ7-Pad79)") (class "Default")
      (node (ref "IC3") (pin "79") (pinfunction "PJ7_79") (pintype "bidirectional"))
    )
    (net (code "104") (name "unconnected-(IC3-PK0(ADC8{slash}PCINT16)-Pad89)") (class "Default")
      (node (ref "IC3") (pin "89") (pinfunction "PK0(ADC8/PCINT16)_89") (pintype "bidirectional"))
    )
    (net (code "105") (name "unconnected-(IC3-PK1(ADC9{slash}PCINT17)-Pad88)") (class "Default")
      (node (ref "IC3") (pin "88") (pinfunction "PK1(ADC9/PCINT17)_88") (pintype "bidirectional"))
    )
    (net (code "106") (name "unconnected-(IC3-PK2(ADC10{slash}PCINT18)-Pad87)") (class "Default")
      (node (ref "IC3") (pin "87") (pinfunction "PK2(ADC10/PCINT18)_87") (pintype "bidirectional"))
    )
    (net (code "107") (name "unconnected-(IC3-PK3(ADC11{slash}PCINT19)-Pad86)") (class "Default")
      (node (ref "IC3") (pin "86") (pinfunction "PK3(ADC11/PCINT19)_86") (pintype "bidirectional"))
    )
    (net (code "108") (name "unconnected-(IC3-PK4(ADC12{slash}PCINT20)-Pad85)") (class "Default")
      (node (ref "IC3") (pin "85") (pinfunction "PK4(ADC12/PCINT20)_85") (pintype "bidirectional"))
    )
    (net (code "109") (name "unconnected-(IC3-PK5(ADC13{slash}PCINT21)-Pad84)") (class "Default")
      (node (ref "IC3") (pin "84") (pinfunction "PK5(ADC13/PCINT21)_84") (pintype "bidirectional"))
    )
    (net (code "110") (name "unconnected-(IC3-PK6(ADC14{slash}PCINT22)-Pad83)") (class "Default")
      (node (ref "IC3") (pin "83") (pinfunction "PK6(ADC14/PCINT22)_83") (pintype "bidirectional"))
    )
    (net (code "111") (name "unconnected-(IC3-PK7(ADC15{slash}PCINT23)-Pad82)") (class "Default")
      (node (ref "IC3") (pin "82") (pinfunction "PK7(ADC15/PCINT23)_82") (pintype "bidirectional"))
    )
    (net (code "112") (name "unconnected-(IC3-PL0(ICP4)-Pad35)") (class "Default")
      (node (ref "IC3") (pin "35") (pinfunction "PL0(ICP4)_35") (pintype "bidirectional"))
    )
    (net (code "113") (name "unconnected-(IC3-PL1(ICP5)-Pad36)") (class "Default")
      (node (ref "IC3") (pin "36") (pinfunction "PL1(ICP5)_36") (pintype "bidirectional"))
    )
    (net (code "114") (name "unconnected-(IC3-PL2(T5)-Pad37)") (class "Default")
      (node (ref "IC3") (pin "37") (pinfunction "PL2(T5)_37") (pintype "bidirectional"))
    )
    (net (code "115") (name "unconnected-(IC3-PL3(OC5A)-Pad38)") (class "Default")
      (node (ref "IC3") (pin "38") (pinfunction "PL3(OC5A)_38") (pintype "bidirectional"))
    )
    (net (code "116") (name "unconnected-(IC3-PL4(OC5B)-Pad39)") (class "Default")
      (node (ref "IC3") (pin "39") (pinfunction "PL4(OC5B)_39") (pintype "bidirectional"))
    )
    (net (code "117") (name "unconnected-(IC3-PL5(OC5C)-Pad40)") (class "Default")
      (node (ref "IC3") (pin "40") (pinfunction "PL5(OC5C)_40") (pintype "bidirectional"))
    )
    (net (code "118") (name "unconnected-(IC3-PL6-Pad41)") (class "Default")
      (node (ref "IC3") (pin "41") (pinfunction "PL6_41") (pintype "bidirectional"))
    )
    (net (code "119") (name "unconnected-(IC3-PL7-Pad42)") (class "Default")
      (node (ref "IC3") (pin "42") (pinfunction "PL7_42") (pintype "bidirectional"))
    )
    (net (code "120") (name "unconnected-(JP4-Pad3)") (class "Default")
      (node (ref "JP4") (pin "3") (pinfunction "3_3") (pintype "passive"))
    )
    (net (code "121") (name "unconnected-(JP6-Pad3)") (class "Default")
      (node (ref "JP6") (pin "3") (pinfunction "3_3") (pintype "passive"))
    )
    (net (code "122") (name "unconnected-(JP7-Pad3)") (class "Default")
      (node (ref "JP7") (pin "3") (pinfunction "3_3") (pintype "passive"))
    )
    (net (code "123") (name "unconnected-(JP8-Pad3)") (class "Default")
      (node (ref "JP8") (pin "3") (pinfunction "3_3") (pintype "passive"))
    )
    (net (code "124") (name "unconnected-(JP9-Pad1)") (class "Default")
      (node (ref "JP9") (pin "1") (pinfunction "1_1") (pintype "passive"))
    )
    (net (code "125") (name "unconnected-(JP9-Pad2)") (class "Default")
      (node (ref "JP9") (pin "2") (pinfunction "2_2") (pintype "passive"))
    )
    (net (code "126") (name "unconnected-(JP9-Pad3)") (class "Default")
      (node (ref "JP9") (pin "3") (pinfunction "3_3") (pintype "passive"))
    )
    (net (code "127") (name "unconnected-(JP9-Pad4)") (class "Default")
      (node (ref "JP9") (pin "4") (pinfunction "4_4") (pintype "passive"))
    )
    (net (code "128") (name "unconnected-(JP9-Pad5)") (class "Default")
      (node (ref "JP9") (pin "5") (pinfunction "5_5") (pintype "passive"))
    )
    (net (code "129") (name "unconnected-(JP10-Pad1)") (class "Default")
      (node (ref "JP10") (pin "1") (pinfunction "1_1") (pintype "passive"))
    )
    (net (code "130") (name "unconnected-(JP10-Pad2)") (class "Default")
      (node (ref "JP10") (pin "2") (pinfunction "2_2") (pintype "passive"))
    )
    (net (code "131") (name "unconnected-(JP10-Pad3)") (class "Default")
      (node (ref "JP10") (pin "3") (pinfunction "3_3") (pintype "passive"))
    )
    (net (code "132") (name "unconnected-(JP10-Pad4)") (class "Default")
      (node (ref "JP10") (pin "4") (pinfunction "4_4") (pintype "passive"))
    )
    (net (code "133") (name "unconnected-(JP10-Pad5)") (class "Default")
      (node (ref "JP10") (pin "5") (pinfunction "5_5") (pintype "passive"))
    )
    (net (code "134") (name "unconnected-(JP11-Pad1)") (class "Default")
      (node (ref "JP11") (pin "1") (pinfunction "1_1") (pintype "passive"))
    )
    (net (code "135") (name "unconnected-(JP11-Pad2)") (class "Default")
      (node (ref "JP11") (pin "2") (pinfunction "2_2") (pintype "passive"))
    )
    (net (code "136") (name "unconnected-(JP11-Pad3)") (class "Default")
      (node (ref "JP11") (pin "3") (pinfunction "3_3") (pintype "passive"))
    )
    (net (code "137") (name "unconnected-(JP11-Pad4)") (class "Default")
      (node (ref "JP11") (pin "4") (pinfunction "4_4") (pintype "passive"))
    )
    (net (code "138") (name "unconnected-(JP11-Pad5)") (class "Default")
      (node (ref "JP11") (pin "5") (pinfunction "5_5") (pintype "passive"))
    )
    (net (code "139") (name "unconnected-(JP12-Pad1)") (class "Default")
      (node (ref "JP12") (pin "1") (pinfunction "1_1") (pintype "passive"))
    )
    (net (code "140") (name "unconnected-(JP12-Pad2)") (class "Default")
      (node (ref "JP12") (pin "2") (pinfunction "2_2") (pintype "passive"))
    )
    (net (code "141") (name "unconnected-(JP12-Pad3)") (class "Default")
      (node (ref "JP12") (pin "3") (pinfunction "3_3") (pintype "passive"))
    )
    (net (code "142") (name "unconnected-(JP12-Pad4)") (class "Default")
      (node (ref "JP12") (pin "4") (pinfunction "4_4") (pintype "passive"))
    )
    (net (code "143") (name "unconnected-(JP12-Pad5)") (class "Default")
      (node (ref "JP12") (pin "5") (pinfunction "5_5") (pintype "passive"))
    )
    (net (code "144") (name "unconnected-(U1-CCP2{slash}P2A{slash}T1CKI{slash}T1OSI{slash}OSC1{slash}CLKIN{slash}RA5-Pad2)") (class "Default")
      (node (ref "U1") (pin "2") (pinfunction "CCP2/P2A/T1CKI/T1OSI/OSC1/CLKIN/RA5_2") (pintype "bidirectional"))
    )
    (net (code "145") (name "unconnected-(U1-MDOUT{slash}CK{slash}TX{slash}P1B{slash}SRNQ{slash}C2OUT{slash}RC4-Pad6)") (class "Default")
      (node (ref "U1") (pin "6") (pinfunction "MDOUT/CK/TX/P1B/SRNQ/C2OUT/RC4_6") (pintype "bidirectional"))
    )
    (net (code "146") (name "unconnected-(U1-RA2{slash}AN2{slash}CPS2{slash}T0CKI{slash}INT{slash}C1OUT{slash}SRQ{slash}CCP3{slash}FLT0-Pad11)") (class "Default")
      (node (ref "U1") (pin "11") (pinfunction "RA2/AN2/CPS2/T0CKI/INT/C1OUT/SRQ/CCP3/FLT0_11") (pintype "bidirectional"))
    )
    (net (code "147") (name "unconnected-(U1-RC0{slash}AN4{slash}CPS4{slash}C2IN+{slash}SCL{slash}SCK{slash}P1D-Pad10)") (class "Default")
      (node (ref "U1") (pin "10") (pinfunction "RC0/AN4/CPS4/C2IN+/SCL/SCK/P1D_10") (pintype "bidirectional"))
    )
    (net (code "148") (name "unconnected-(U1-T1G{slash}P2B{slash}SDO{slash}CLKR{slash}T1OSO{slash}CLKOUT{slash}OSC2{slash}CPS3{slash}AN3{slash}RA4-Pad3)") (class "Default")
      (node (ref "U1") (pin "3") (pinfunction "T1G/P2B/SDO/CLKR/T1OSO/CLKOUT/OSC2/CPS3/AN3/RA4_3") (pintype "bidirectional"))
    )
  )
)
